# Top_level.net
KiCad netlist of a schematic drawn in Altium Designer
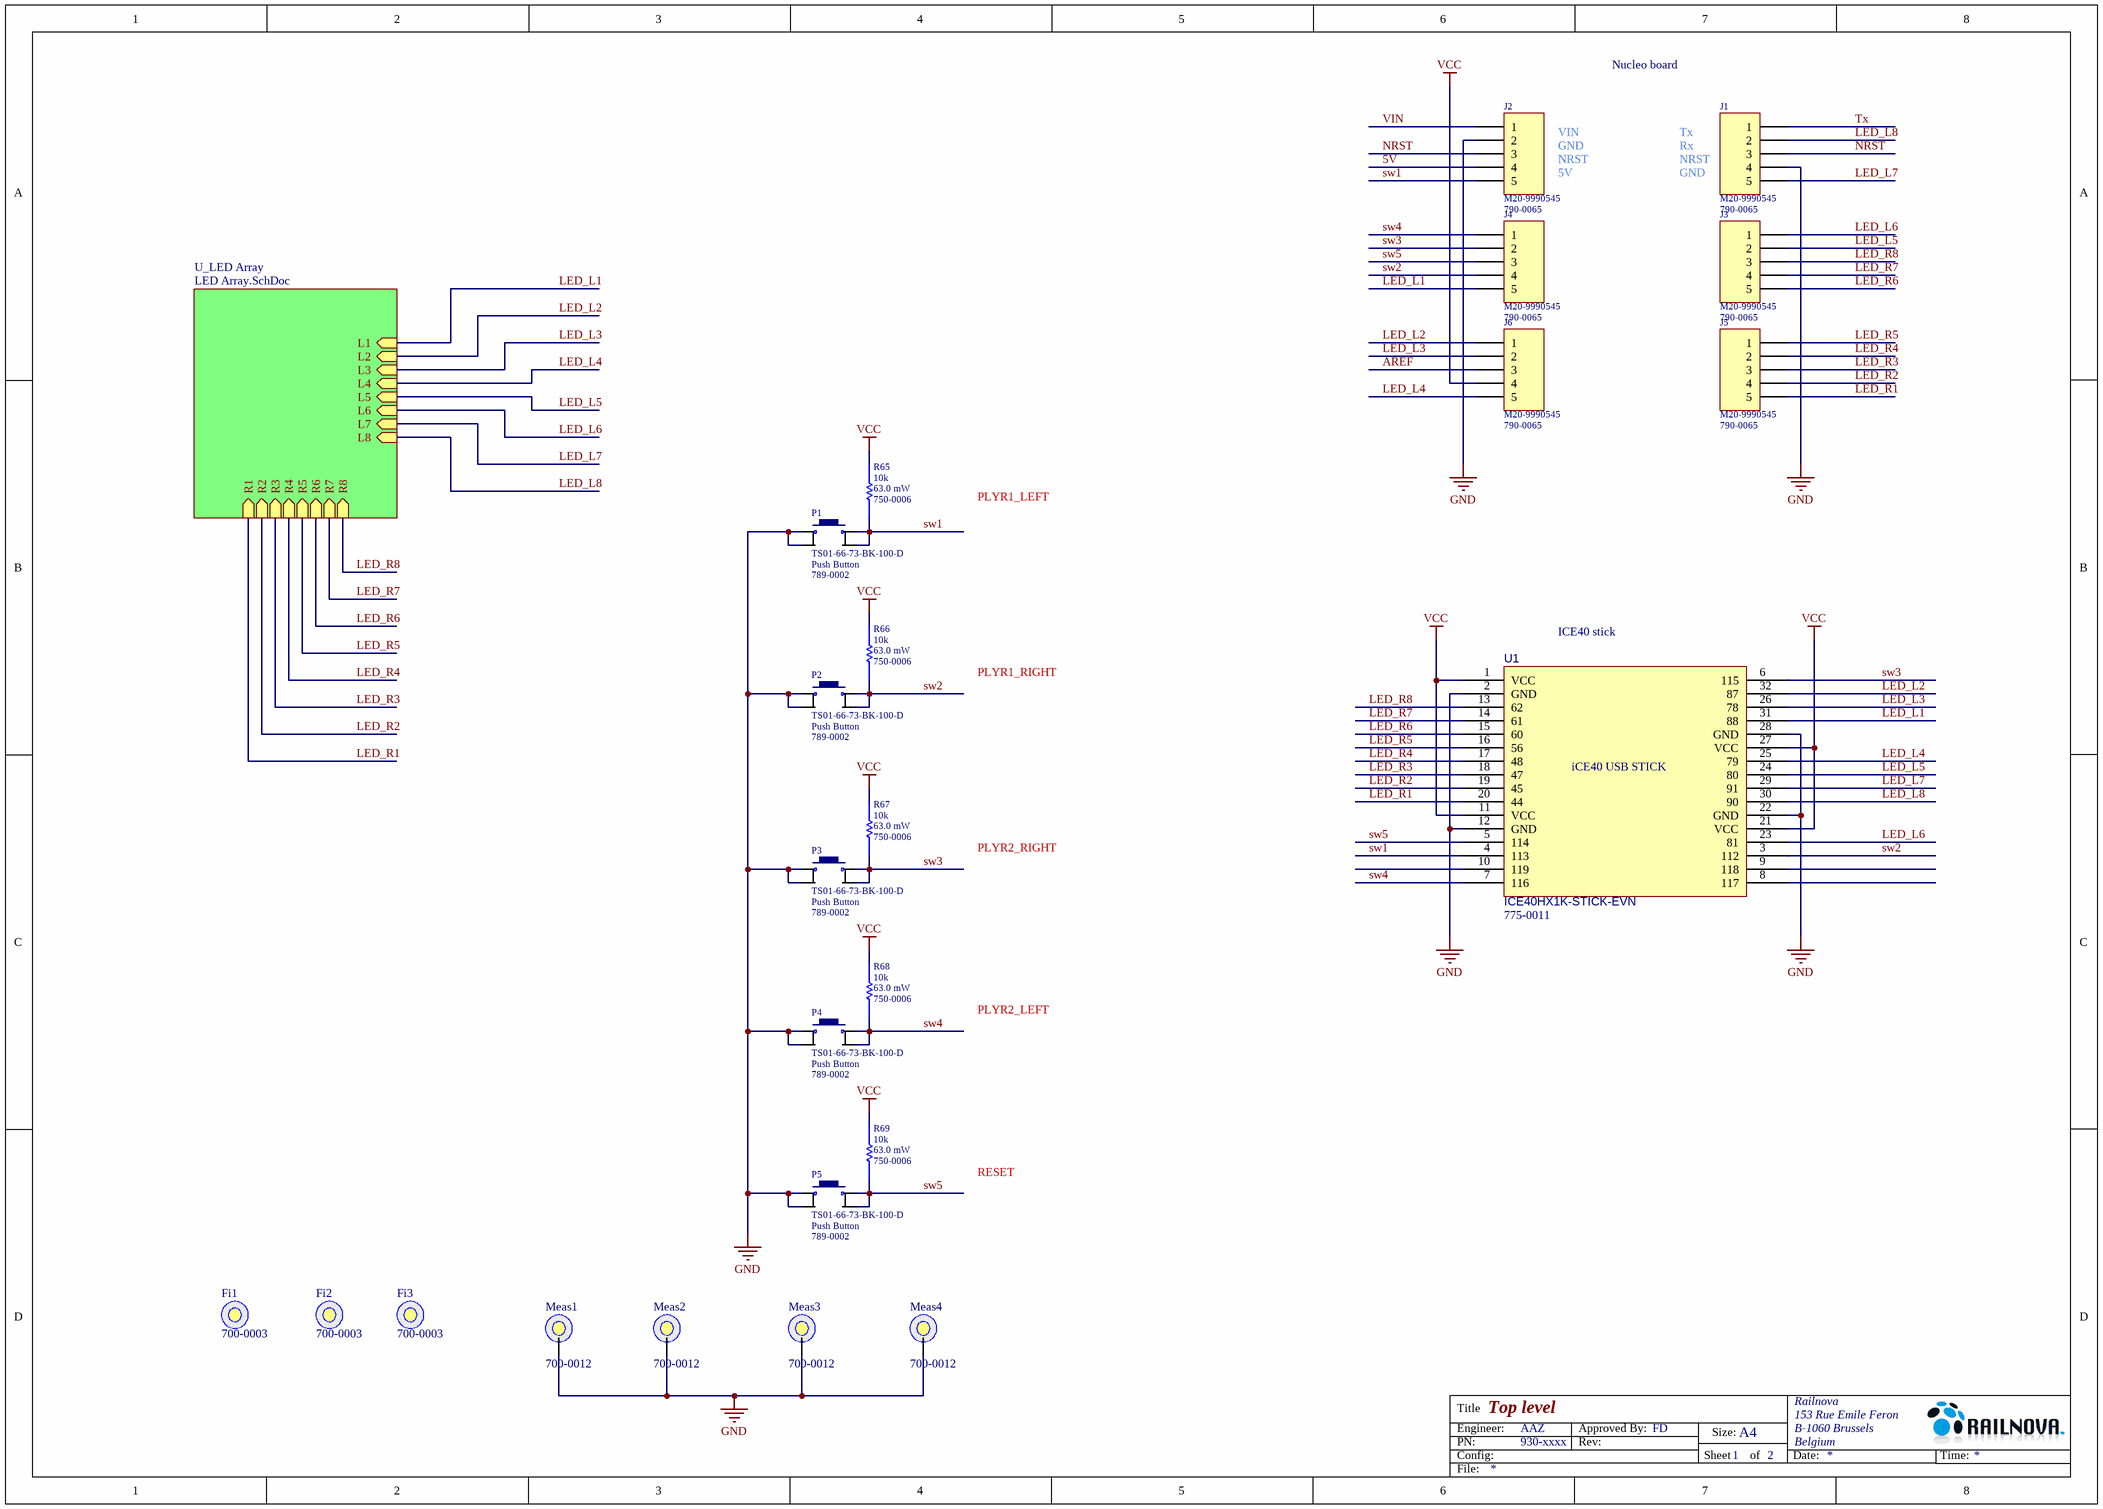
[diagram p0: Top level.SchDoc]

(export (version "E")
  (design (tool "Eeschema 10.0.6"))
  (components
    (comp (ref "Fi1")
      (value "700-0003")
      (footprint "Fiducial_1mm")
      (description "Fiducial")
      (libsource (lib "rnlib2") (part "Fiducial_1mm"))
    )
    (comp (ref "Fi2")
      (value "700-0003")
      (footprint "Fiducial_1mm")
      (description "Fiducial")
      (libsource (lib "rnlib2") (part "Fiducial_1mm"))
    )
    (comp (ref "Fi3")
      (value "700-0003")
      (footprint "Fiducial_1mm")
      (description "Fiducial")
      (libsource (lib "rnlib2") (part "Fiducial_1mm"))
    )
    (comp (ref "J1")
      (value "M20-9990545")
      (footprint "CON-HDR-VER-M1X5")
      (description "CONN REC HDR VERTICAL MALE 1X5 P0.1in")
      (fields (field (name "PART NUMBER") "790-0065") (field (name "MANUFACTURER") "HARWIN"))
      (libsource (lib "rnlib2") (part "CON-1X5_HDR"))
    )
    (comp (ref "J2")
      (value "M20-9990545")
      (footprint "CON-HDR-VER-M1X5")
      (description "CONN REC HDR VERTICAL MALE 1X5 P0.1in")
      (fields (field (name "PART NUMBER") "790-0065") (field (name "MANUFACTURER") "HARWIN"))
      (libsource (lib "") (part "CON-1X5_HDR_1"))
    )
    (comp (ref "J3")
      (value "M20-9990545")
      (footprint "CON-HDR-VER-M1X5")
      (description "CONN REC HDR VERTICAL MALE 1X5 P0.1in")
      (fields (field (name "PART NUMBER") "790-0065") (field (name "MANUFACTURER") "HARWIN"))
      (libsource (lib "rnlib2") (part "CON-1X5_HDR"))
    )
    (comp (ref "J4")
      (value "M20-9990545")
      (footprint "CON-HDR-VER-M1X5")
      (description "CONN REC HDR VERTICAL MALE 1X5 P0.1in")
      (fields (field (name "PART NUMBER") "790-0065") (field (name "MANUFACTURER") "HARWIN"))
      (libsource (lib "") (part "CON-1X5_HDR_1"))
    )
    (comp (ref "J5")
      (value "M20-9990545")
      (footprint "CON-HDR-VER-M1X5")
      (description "CONN REC HDR VERTICAL MALE 1X5 P0.1in")
      (fields (field (name "PART NUMBER") "790-0065") (field (name "MANUFACTURER") "HARWIN"))
      (libsource (lib "rnlib2") (part "CON-1X5_HDR"))
    )
    (comp (ref "J6")
      (value "M20-9990545")
      (footprint "CON-HDR-VER-M1X5")
      (description "CONN REC HDR VERTICAL MALE 1X5 P0.1in")
      (fields (field (name "PART NUMBER") "790-0065") (field (name "MANUFACTURER") "HARWIN"))
      (libsource (lib "") (part "CON-1X5_HDR_1"))
    )
    (comp (ref "Meas1")
      (value "700-0012")
      (footprint "FOX_measure_point_3mm")
      (description "Measuring point for FOX, 3mm without soldermask")
      (fields (field (name "MPN") "MeasurePoint"))
      (libsource (lib "rnlib2") (part "FOX_measure_point_3mm"))
    )
    (comp (ref "Meas2")
      (value "700-0012")
      (footprint "FOX_measure_point_3mm")
      (description "Measuring point for FOX, 3mm without soldermask")
      (fields (field (name "MPN") "MeasurePoint"))
      (libsource (lib "rnlib2") (part "FOX_measure_point_3mm"))
    )
    (comp (ref "Meas3")
      (value "700-0012")
      (footprint "FOX_measure_point_3mm")
      (description "Measuring point for FOX, 3mm without soldermask")
      (fields (field (name "MPN") "MeasurePoint"))
      (libsource (lib "rnlib2") (part "FOX_measure_point_3mm"))
    )
    (comp (ref "Meas4")
      (value "700-0012")
      (footprint "FOX_measure_point_3mm")
      (description "Measuring point for FOX, 3mm without soldermask")
      (fields (field (name "MPN") "MeasurePoint"))
      (libsource (lib "rnlib2") (part "FOX_measure_point_3mm"))
    )
    (comp (ref "P1")
      (value "TS01-66-73-BK-100-D")
      (footprint "TS01-66-70-BK")
      (description "Push Button 6 x 6 mm, 7 mm Act Height, 100 gf, Black, Short Crimped, Through Hole, SPST")
      (fields (field (name "COMPONENT TYPE") "Push Button") (field (name "PART NUMBER") "789-0002"))
      (libsource (lib "rnlib2") (part "TS01-66-73-BK-100-D"))
    )
    (comp (ref "P2")
      (value "TS01-66-73-BK-100-D")
      (footprint "TS01-66-70-BK")
      (description "Push Button 6 x 6 mm, 7 mm Act Height, 100 gf, Black, Short Crimped, Through Hole, SPST")
      (fields (field (name "COMPONENT TYPE") "Push Button") (field (name "PART NUMBER") "789-0002"))
      (libsource (lib "rnlib2") (part "TS01-66-73-BK-100-D"))
    )
    (comp (ref "P3")
      (value "TS01-66-73-BK-100-D")
      (footprint "TS01-66-70-BK")
      (description "Push Button 6 x 6 mm, 7 mm Act Height, 100 gf, Black, Short Crimped, Through Hole, SPST")
      (fields (field (name "COMPONENT TYPE") "Push Button") (field (name "PART NUMBER") "789-0002"))
      (libsource (lib "rnlib2") (part "TS01-66-73-BK-100-D"))
    )
    (comp (ref "P4")
      (value "TS01-66-73-BK-100-D")
      (footprint "TS01-66-70-BK")
      (description "Push Button 6 x 6 mm, 7 mm Act Height, 100 gf, Black, Short Crimped, Through Hole, SPST")
      (fields (field (name "COMPONENT TYPE") "Push Button") (field (name "PART NUMBER") "789-0002"))
      (libsource (lib "rnlib2") (part "TS01-66-73-BK-100-D"))
    )
    (comp (ref "P5")
      (value "TS01-66-73-BK-100-D")
      (footprint "TS01-66-70-BK")
      (description "Push Button 6 x 6 mm, 7 mm Act Height, 100 gf, Black, Short Crimped, Through Hole, SPST")
      (fields (field (name "COMPONENT TYPE") "Push Button") (field (name "PART NUMBER") "789-0002"))
      (libsource (lib "rnlib2") (part "TS01-66-73-BK-100-D"))
    )
    (comp (ref "R65")
      (value "10k")
      (footprint "R0402-IPC-MD")
      (description "Resistor 10k 0402 1% 63.0 mW")
      (fields
        (field (name "PMAX") "63.0 mW")
        (field (name "PART NUMBER") "750-0006")
        (field (name "MPN") "CRCW040210K0FKED")
        (field (name "MANUFACTURER") "VISHAY")
      )
      (libsource (lib "rnlib2") (part "Resistors"))
    )
    (comp (ref "R66")
      (value "10k")
      (footprint "R0402-IPC-MD")
      (description "Resistor 10k 0402 1% 63.0 mW")
      (fields
        (field (name "PMAX") "63.0 mW")
        (field (name "PART NUMBER") "750-0006")
        (field (name "MPN") "CRCW040210K0FKED")
        (field (name "MANUFACTURER") "VISHAY")
      )
      (libsource (lib "rnlib2") (part "Resistors"))
    )
    (comp (ref "R67")
      (value "10k")
      (footprint "R0402-IPC-MD")
      (description "Resistor 10k 0402 1% 63.0 mW")
      (fields
        (field (name "PMAX") "63.0 mW")
        (field (name "PART NUMBER") "750-0006")
        (field (name "MPN") "CRCW040210K0FKED")
        (field (name "MANUFACTURER") "VISHAY")
      )
      (libsource (lib "rnlib2") (part "Resistors"))
    )
    (comp (ref "R68")
      (value "10k")
      (footprint "R0402-IPC-MD")
      (description "Resistor 10k 0402 1% 63.0 mW")
      (fields
        (field (name "PMAX") "63.0 mW")
        (field (name "PART NUMBER") "750-0006")
        (field (name "MPN") "CRCW040210K0FKED")
        (field (name "MANUFACTURER") "VISHAY")
      )
      (libsource (lib "rnlib2") (part "Resistors"))
    )
    (comp (ref "R69")
      (value "10k")
      (footprint "R0402-IPC-MD")
      (description "Resistor 10k 0402 1% 63.0 mW")
      (fields
        (field (name "PMAX") "63.0 mW")
        (field (name "PART NUMBER") "750-0006")
        (field (name "MPN") "CRCW040210K0FKED")
        (field (name "MANUFACTURER") "VISHAY")
      )
      (libsource (lib "rnlib2") (part "Resistors"))
    )
    (comp (ref "U1")
      (value "ICE40HX1K-STICK-EVN")
      (footprint "ICE-stick")
      (description "iCE40 FPGA USB stick")
      (fields
        (field (name "MANUFACTURER") "LATTICE SEMICONDUCTOR")
        (field (name "PART NUMBER") "775-0011")
        (field (name "REVISION NOTE") "Created by Abdellah Azaanoun")
      )
      (libsource (lib "rnlib2") (part "ICE-stick"))
    )
  )
  (nets
    (net (code "1") (name "/5V") (class "Default")
      (node (ref "J2") (pin "4") (pinfunction "4_4") (pintype "passive"))
    )
    (net (code "2") (name "/AREF") (class "Default")
      (node (ref "J6") (pin "3") (pinfunction "3_3") (pintype "passive"))
    )
    (net (code "3") (name "/LED_L1") (class "Default")
      (node (ref "J4") (pin "5") (pinfunction "5_5") (pintype "passive"))
      (node (ref "U1") (pin "31") (pinfunction "88_31") (pintype "passive"))
    )
    (net (code "4") (name "/LED_L2") (class "Default")
      (node (ref "J6") (pin "1") (pinfunction "1_1") (pintype "passive"))
      (node (ref "U1") (pin "32") (pinfunction "87_32") (pintype "passive"))
    )
    (net (code "5") (name "/LED_L3") (class "Default")
      (node (ref "J6") (pin "2") (pinfunction "2_2") (pintype "passive"))
      (node (ref "U1") (pin "26") (pinfunction "78_26") (pintype "passive"))
    )
    (net (code "6") (name "/LED_L4") (class "Default")
      (node (ref "J6") (pin "5") (pinfunction "5_5") (pintype "passive"))
      (node (ref "U1") (pin "25") (pinfunction "79_25") (pintype "passive"))
    )
    (net (code "7") (name "/LED_L5") (class "Default")
      (node (ref "J3") (pin "2") (pinfunction "2_2") (pintype "passive"))
      (node (ref "U1") (pin "24") (pinfunction "80_24") (pintype "passive"))
    )
    (net (code "8") (name "/LED_L6") (class "Default")
      (node (ref "J3") (pin "1") (pinfunction "1_1") (pintype "passive"))
      (node (ref "U1") (pin "23") (pinfunction "81_23") (pintype "passive"))
    )
    (net (code "9") (name "/LED_L7") (class "Default")
      (node (ref "J1") (pin "5") (pinfunction "5_5") (pintype "passive"))
      (node (ref "U1") (pin "29") (pinfunction "91_29") (pintype "passive"))
    )
    (net (code "10") (name "/LED_L8") (class "Default")
      (node (ref "J1") (pin "2") (pinfunction "2_2") (pintype "passive"))
      (node (ref "U1") (pin "30") (pinfunction "90_30") (pintype "passive"))
    )
    (net (code "11") (name "/LED_R1") (class "Default")
      (node (ref "J5") (pin "5") (pinfunction "5_5") (pintype "passive"))
      (node (ref "U1") (pin "20") (pinfunction "44_20") (pintype "passive"))
    )
    (net (code "12") (name "/LED_R2") (class "Default")
      (node (ref "J5") (pin "4") (pinfunction "4_4") (pintype "passive"))
      (node (ref "U1") (pin "19") (pinfunction "45_19") (pintype "passive"))
    )
    (net (code "13") (name "/LED_R3") (class "Default")
      (node (ref "J5") (pin "3") (pinfunction "3_3") (pintype "passive"))
      (node (ref "U1") (pin "18") (pinfunction "47_18") (pintype "passive"))
    )
    (net (code "14") (name "/LED_R4") (class "Default")
      (node (ref "J5") (pin "2") (pinfunction "2_2") (pintype "passive"))
      (node (ref "U1") (pin "17") (pinfunction "48_17") (pintype "passive"))
    )
    (net (code "15") (name "/LED_R5") (class "Default")
      (node (ref "J5") (pin "1") (pinfunction "1_1") (pintype "passive"))
      (node (ref "U1") (pin "16") (pinfunction "56_16") (pintype "passive"))
    )
    (net (code "16") (name "/LED_R6") (class "Default")
      (node (ref "J3") (pin "5") (pinfunction "5_5") (pintype "passive"))
      (node (ref "U1") (pin "15") (pinfunction "60_15") (pintype "passive"))
    )
    (net (code "17") (name "/LED_R7") (class "Default")
      (node (ref "J3") (pin "4") (pinfunction "4_4") (pintype "passive"))
      (node (ref "U1") (pin "14") (pinfunction "61_14") (pintype "passive"))
    )
    (net (code "18") (name "/LED_R8") (class "Default")
      (node (ref "J3") (pin "3") (pinfunction "3_3") (pintype "passive"))
      (node (ref "U1") (pin "13") (pinfunction "62_13") (pintype "passive"))
    )
    (net (code "19") (name "/NRST") (class "Default")
      (node (ref "J1") (pin "3") (pinfunction "3_3") (pintype "passive"))
      (node (ref "J2") (pin "3") (pinfunction "3_3") (pintype "passive"))
    )
    (net (code "20") (name "/Tx") (class "Default")
      (node (ref "J1") (pin "1") (pinfunction "1_1") (pintype "passive"))
    )
    (net (code "21") (name "/VIN") (class "Default")
      (node (ref "J2") (pin "1") (pinfunction "1_1") (pintype "passive"))
    )
    (net (code "22") (name "/sw1") (class "Default")
      (node (ref "J2") (pin "5") (pinfunction "5_5") (pintype "passive"))
      (node (ref "P1") (pin "3") (pinfunction "3_3") (pintype "passive"))
      (node (ref "P1") (pin "4") (pinfunction "4_4") (pintype "passive"))
      (node (ref "R65") (pin "1") (pinfunction "1_1") (pintype "passive"))
      (node (ref "U1") (pin "4") (pinfunction "113_4") (pintype "passive"))
    )
    (net (code "23") (name "/sw2") (class "Default")
      (node (ref "J4") (pin "4") (pinfunction "4_4") (pintype "passive"))
      (node (ref "P2") (pin "3") (pinfunction "3_3") (pintype "passive"))
      (node (ref "P2") (pin "4") (pinfunction "4_4") (pintype "passive"))
      (node (ref "R66") (pin "1") (pinfunction "1_1") (pintype "passive"))
      (node (ref "U1") (pin "3") (pinfunction "112_3") (pintype "passive"))
    )
    (net (code "24") (name "/sw3") (class "Default")
      (node (ref "J4") (pin "2") (pinfunction "2_2") (pintype "passive"))
      (node (ref "P3") (pin "3") (pinfunction "3_3") (pintype "passive"))
      (node (ref "P3") (pin "4") (pinfunction "4_4") (pintype "passive"))
      (node (ref "R67") (pin "1") (pinfunction "1_1") (pintype "passive"))
      (node (ref "U1") (pin "6") (pinfunction "115_6") (pintype "passive"))
    )
    (net (code "25") (name "/sw4") (class "Default")
      (node (ref "J4") (pin "1") (pinfunction "1_1") (pintype "passive"))
      (node (ref "P4") (pin "3") (pinfunction "3_3") (pintype "passive"))
      (node (ref "P4") (pin "4") (pinfunction "4_4") (pintype "passive"))
      (node (ref "R68") (pin "1") (pinfunction "1_1") (pintype "passive"))
      (node (ref "U1") (pin "7") (pinfunction "116_7") (pintype "passive"))
    )
    (net (code "26") (name "/sw5") (class "Default")
      (node (ref "J4") (pin "3") (pinfunction "3_3") (pintype "passive"))
      (node (ref "P5") (pin "3") (pinfunction "3_3") (pintype "passive"))
      (node (ref "P5") (pin "4") (pinfunction "4_4") (pintype "passive"))
      (node (ref "R69") (pin "1") (pinfunction "1_1") (pintype "passive"))
      (node (ref "U1") (pin "5") (pinfunction "114_5") (pintype "passive"))
    )
    (net (code "27") (name "GND") (class "Default")
      (node (ref "J1") (pin "4") (pinfunction "4_4") (pintype "passive"))
      (node (ref "J2") (pin "2") (pinfunction "2_2") (pintype "passive"))
      (node (ref "Meas1") (pin "pad") (pinfunction "GND_pad") (pintype "passive"))
      (node (ref "Meas2") (pin "pad") (pinfunction "GND_pad") (pintype "passive"))
      (node (ref "Meas3") (pin "pad") (pinfunction "GND_pad") (pintype "passive"))
      (node (ref "Meas4") (pin "pad") (pinfunction "GND_pad") (pintype "passive"))
      (node (ref "P1") (pin "1") (pinfunction "1_1") (pintype "passive"))
      (node (ref "P1") (pin "2") (pinfunction "2_2") (pintype "passive"))
      (node (ref "P2") (pin "1") (pinfunction "1_1") (pintype "passive"))
      (node (ref "P2") (pin "2") (pinfunction "2_2") (pintype "passive"))
      (node (ref "P3") (pin "1") (pinfunction "1_1") (pintype "passive"))
      (node (ref "P3") (pin "2") (pinfunction "2_2") (pintype "passive"))
      (node (ref "P4") (pin "1") (pinfunction "1_1") (pintype "passive"))
      (node (ref "P4") (pin "2") (pinfunction "2_2") (pintype "passive"))
      (node (ref "P5") (pin "1") (pinfunction "1_1") (pintype "passive"))
      (node (ref "P5") (pin "2") (pinfunction "2_2") (pintype "passive"))
      (node (ref "U1") (pin "12") (pinfunction "GND_12") (pintype "passive"))
      (node (ref "U1") (pin "2") (pinfunction "GND_2") (pintype "passive"))
      (node (ref "U1") (pin "22") (pinfunction "GND_22") (pintype "passive"))
      (node (ref "U1") (pin "28") (pinfunction "GND_28") (pintype "passive"))
    )
    (net (code "28") (name "VCC") (class "Default")
      (node (ref "J6") (pin "4") (pinfunction "4_4") (pintype "passive"))
      (node (ref "R65") (pin "2") (pinfunction "2_2") (pintype "passive"))
      (node (ref "R66") (pin "2") (pinfunction "2_2") (pintype "passive"))
      (node (ref "R67") (pin "2") (pinfunction "2_2") (pintype "passive"))
      (node (ref "R68") (pin "2") (pinfunction "2_2") (pintype "passive"))
      (node (ref "R69") (pin "2") (pinfunction "2_2") (pintype "passive"))
      (node (ref "U1") (pin "1") (pinfunction "VCC_1") (pintype "passive"))
      (node (ref "U1") (pin "11") (pinfunction "VCC_11") (pintype "passive"))
      (node (ref "U1") (pin "21") (pinfunction "VCC_21") (pintype "passive"))
      (node (ref "U1") (pin "27") (pinfunction "VCC_27") (pintype "passive"))
    )
    (net (code "29") (name "unconnected-(U1-117-Pad8)") (class "Default")
      (node (ref "U1") (pin "8") (pinfunction "117_8") (pintype "passive"))
    )
    (net (code "30") (name "unconnected-(U1-118-Pad9)") (class "Default")
      (node (ref "U1") (pin "9") (pinfunction "118_9") (pintype "passive"))
    )
    (net (code "31") (name "unconnected-(U1-119-Pad10)") (class "Default")
      (node (ref "U1") (pin "10") (pinfunction "119_10") (pintype "passive"))
    )
  )
)
